# MDBT42Q.net
KiCad netlist of a schematic drawn in Altium Designer
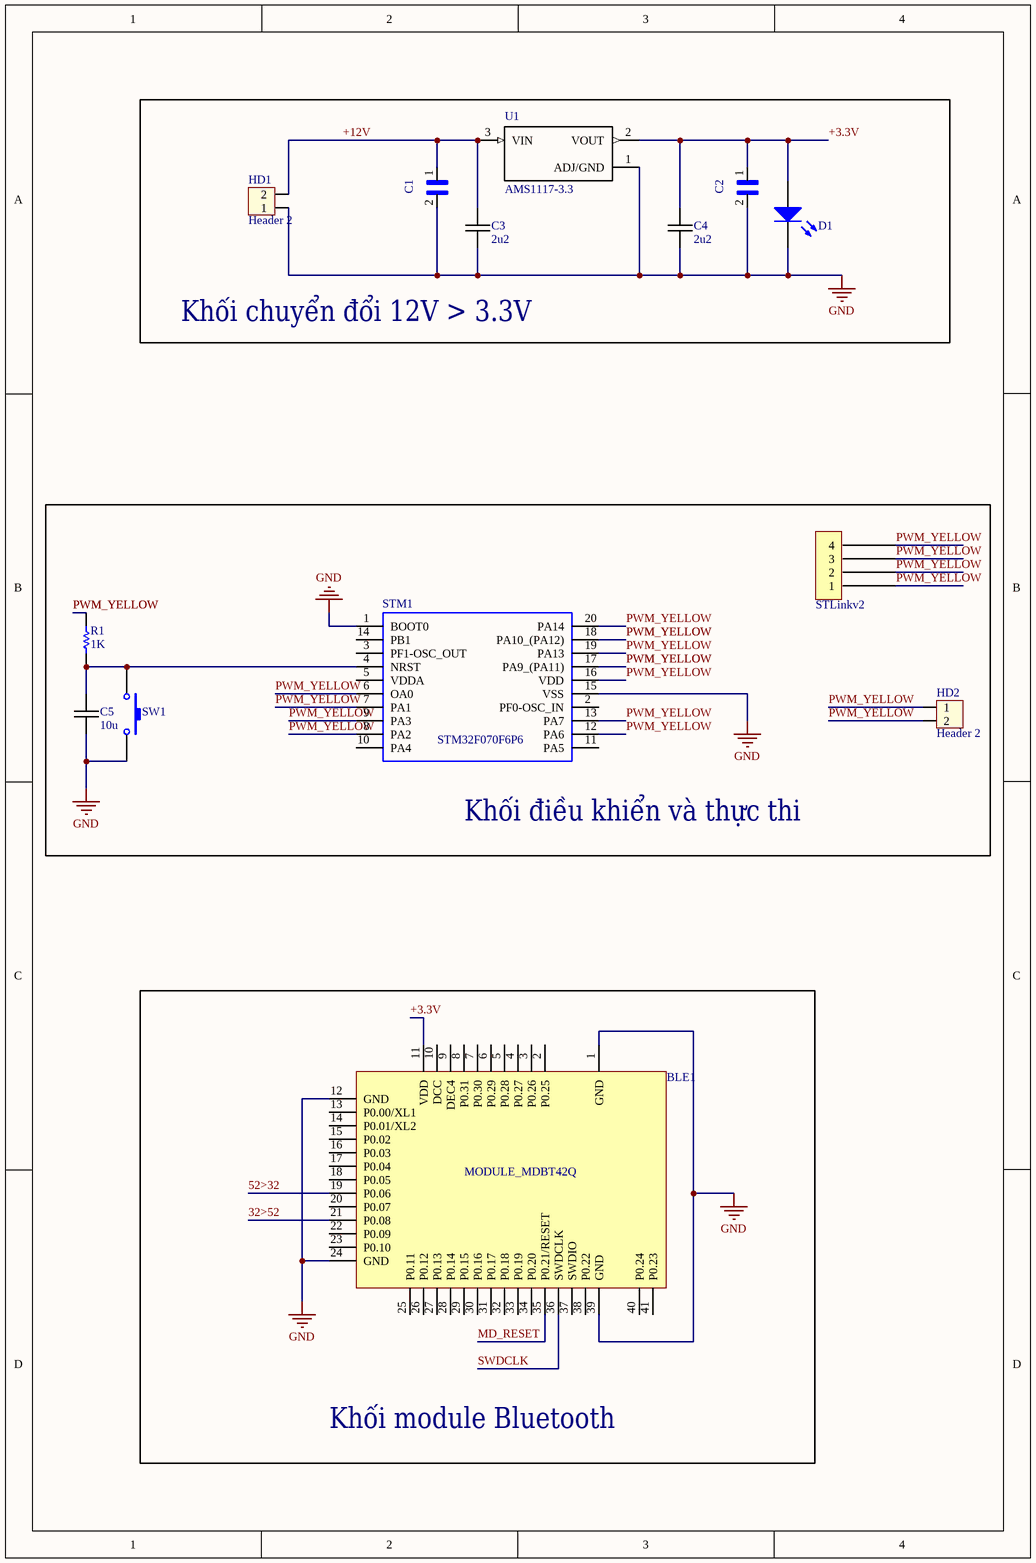
[diagram p0: MDBT42Q.SchDoc]

(export (version "E")
  (design (tool "Eeschema 10.0.6"))
  (components
    (comp (ref "BLE1")
      (value "MODULE_MDBT42Q")
      (footprint "PCB_MDBT42Q_10X16")
      (description "MDBT42Q")
      (libsource (lib "MDBT42Q_SCHLIB_160922") (part "MODULE_MDBT42Q"))
    )
    (comp (ref "C1")
      (value "C3216X5R1A106K160AB")
      (footprint "CAPC3216X180")
      (description "C Series 1206 10 uF 10 V Â±10 % Tolerance X5R SMT Multilayer Ceramic Capacitor")
      (fields (field (name "MF") "TDK"))
      (libsource (lib "C3216X5R1A106K160AB") (part "C3216X5R1A106K160AB"))
    )
    (comp (ref "C2")
      (value "C3216X5R1A106K160AB")
      (footprint "CAPC3216X180")
      (description "C Series 1206 10 uF 10 V Â±10 % Tolerance X5R SMT Multilayer Ceramic Capacitor")
      (fields (field (name "MF") "TDK"))
      (libsource (lib "C3216X5R1A106K160AB") (part "C3216X5R1A106K160AB"))
    )
    (comp (ref "C3")
      (value "2u2")
      (footprint "0805C-GENERIC")
      (description "CAPACITOR 0805 CERAMIC")
      (fields
        (field (name "MANUFACTURER PART NUMBER") "ECJ-1VB0J225K")
        (field (name "MANUFACTURER") "Panasonic - ECG")
      )
      (libsource (lib "vh_altium_library") (part "0805C-2U2-6V3-X5R-PAN"))
    )
    (comp (ref "C4")
      (value "2u2")
      (footprint "0805C-GENERIC")
      (description "CAPACITOR 0805 CERAMIC")
      (fields
        (field (name "MANUFACTURER PART NUMBER") "ECJ-1VB0J225K")
        (field (name "MANUFACTURER") "Panasonic - ECG")
      )
      (libsource (lib "vh_altium_library") (part "0805C-2U2-6V3-X5R-PAN"))
    )
    (comp (ref "C5")
      (value "10u")
      (footprint "0805C-GENERIC")
      (description "CAPACITOR 0805 CERAMIC")
      (fields
        (field (name "MANUFACTURER PART NUMBER") "ECJ-1VB0J225K")
        (field (name "MANUFACTURER") "Panasonic - ECG")
      )
      (libsource (lib "vh_altium_library") (part "0805C-2U2-6V3-X5R-PAN"))
    )
    (comp (ref "D1")
      (value "LED SMD")
      (footprint "LED_0805_Blue")
      (description "LED")
      (libsource (lib "PIF_Library") (part "LED SMD"))
    )
    (comp (ref "HD1")
      (value "Header 2")
      (footprint "HED2")
      (description "Header 2 (Green)")
      (libsource (lib "takahashi") (part "Hed2"))
    )
    (comp (ref "HD2")
      (value "Header 2")
      (footprint "HED2")
      (description "Header 2 (Green)")
      (libsource (lib "") (part "Hed2_1"))
    )
    (comp (ref "R1")
      (value "1K")
      (footprint "RES-SM-1206")
      (description "Resistor")
      (fields (field (name "Comment") "RESISTOR SMD"))
      (libsource (lib "PIF_Library") (part "RESISTOR SMD"))
    )
    (comp (ref "STLinkv2")
      (value "JP")
      (footprint "Jumper 4x1")
      (libsource (lib "jumper library Hoang loi") (part "Jumper 4x1"))
    )
    (comp (ref "STM1")
      (value "STM32F070F6P6")
      (footprint "SOP65P640X120-20N")
      (description "STMICROELECTRONICS - STM32F070F6P6 - MCU, 32BIT, CORTEX-M0, 48MHZ, TSSOP-20")
      (libsource (lib "STM32F070F6P6") (part "STM32F070F6P6"))
    )
    (comp (ref "SW1")
      (value "SW")
      (footprint "SW2")
      (description "Switch button 2 pin")
      (libsource (lib "PIF_Library") (part "Tact SW - 2Pin"))
    )
    (comp (ref "U1")
      (value "AMS1117-3.3")
      (footprint "SOT229P700X180-4N")
      (description "Sot223/Pkg 1-Amp 3.3-Volt Low Drop Out Voltage Regulatator")
      (fields (field (name "MF") "Advanced Monolithic Systems"))
      (libsource (lib "AMS1117-3.3") (part "AMS1117-3.3"))
    )
  )
  (nets
    (net (code "1") (name "/+3.3V") (class "Default")
      (node (ref "BLE1") (pin "11") (pinfunction "VDD_11") (pintype "passive"))
      (node (ref "C2") (pin "1") (pinfunction "1_1") (pintype "passive"))
      (node (ref "C4") (pin "1") (pintype "passive"))
      (node (ref "D1") (pin "1") (pinfunction "A_1") (pintype "passive"))
      (node (ref "U1") (pin "2") (pinfunction "VOUT_2") (pintype "output"))
    )
    (net (code "2") (name "/+12V") (class "Default")
      (node (ref "C1") (pin "1") (pinfunction "1_1") (pintype "passive"))
      (node (ref "C3") (pin "1") (pintype "passive"))
      (node (ref "HD1") (pin "2") (pinfunction "2_2") (pintype "passive"))
      (node (ref "U1") (pin "3") (pinfunction "VIN_3") (pintype "input"))
    )
    (net (code "3") (name "/32>52") (class "Default")
      (node (ref "BLE1") (pin "21") (pinfunction "P0.08_21") (pintype "passive"))
    )
    (net (code "4") (name "/52>32") (class "Default")
      (node (ref "BLE1") (pin "19") (pinfunction "P0.06_19") (pintype "passive"))
    )
    (net (code "5") (name "/MD_RESET") (class "Default")
      (node (ref "BLE1") (pin "35") (pinfunction "P0.21/RESET_35") (pintype "passive"))
    )
    (net (code "6") (name "/PWM_YELLOW") (class "Default")
      (node (ref "HD2") (pin "1") (pinfunction "1_1") (pintype "passive"))
      (node (ref "HD2") (pin "2") (pinfunction "2_2") (pintype "passive"))
      (node (ref "R1") (pin "2") (pinfunction "2_2") (pintype "passive"))
      (node (ref "STLinkv2") (pin "1") (pinfunction "1_1") (pintype "passive"))
      (node (ref "STLinkv2") (pin "2") (pinfunction "2_2") (pintype "passive"))
      (node (ref "STLinkv2") (pin "3") (pinfunction "3_3") (pintype "passive"))
      (node (ref "STLinkv2") (pin "4") (pinfunction "4_4") (pintype "passive"))
      (node (ref "STM1") (pin "12") (pinfunction "PA6_12") (pintype "passive"))
      (node (ref "STM1") (pin "13") (pinfunction "PA7_13") (pintype "passive"))
      (node (ref "STM1") (pin "16") (pinfunction "VDD_16") (pintype "passive"))
      (node (ref "STM1") (pin "17") (pinfunction "PA9_(PA11)_17") (pintype "passive"))
      (node (ref "STM1") (pin "18") (pinfunction "PA10_(PA12)_18") (pintype "passive"))
      (node (ref "STM1") (pin "19") (pinfunction "PA13_19") (pintype "passive"))
      (node (ref "STM1") (pin "20") (pinfunction "PA14_20") (pintype "passive"))
      (node (ref "STM1") (pin "6") (pinfunction "OA0_6") (pintype "passive"))
      (node (ref "STM1") (pin "7") (pinfunction "PA1_7") (pintype "passive"))
      (node (ref "STM1") (pin "8") (pinfunction "PA2_8") (pintype "passive"))
      (node (ref "STM1") (pin "9") (pinfunction "PA3_9") (pintype "passive"))
    )
    (net (code "7") (name "/SWDCLK") (class "Default")
      (node (ref "BLE1") (pin "36") (pinfunction "SWDCLK_36") (pintype "passive"))
    )
    (net (code "8") (name "GND") (class "Default")
      (node (ref "BLE1") (pin "1") (pinfunction "GND_1") (pintype "passive"))
      (node (ref "BLE1") (pin "12") (pinfunction "GND_12") (pintype "passive"))
      (node (ref "BLE1") (pin "24") (pinfunction "GND_24") (pintype "passive"))
      (node (ref "BLE1") (pin "39") (pinfunction "GND_39") (pintype "passive"))
      (node (ref "C1") (pin "2") (pinfunction "2_2") (pintype "passive"))
      (node (ref "C2") (pin "2") (pinfunction "2_2") (pintype "passive"))
      (node (ref "C3") (pin "2") (pintype "passive"))
      (node (ref "C4") (pin "2") (pintype "passive"))
      (node (ref "C5") (pin "2") (pintype "passive"))
      (node (ref "D1") (pin "2") (pinfunction "K_2") (pintype "passive"))
      (node (ref "HD1") (pin "1") (pinfunction "1_1") (pintype "passive"))
      (node (ref "STM1") (pin "1") (pinfunction "BOOT0_1") (pintype "passive"))
      (node (ref "STM1") (pin "15") (pinfunction "VSS_15") (pintype "passive"))
      (node (ref "SW1") (pin "2") (pinfunction "2_2") (pintype "passive"))
      (node (ref "U1") (pin "1") (pinfunction "ADJ/GND_1") (pintype "power_in"))
    )
    (net (code "9") (name "Net-(STM1-NRST)") (class "Default")
      (node (ref "C5") (pin "1") (pintype "passive"))
      (node (ref "R1") (pin "1") (pinfunction "1_1") (pintype "passive"))
      (node (ref "STM1") (pin "4") (pinfunction "NRST_4") (pintype "passive"))
      (node (ref "SW1") (pin "1") (pinfunction "1_1") (pintype "passive"))
    )
    (net (code "10") (name "unconnected-(BLE1-DCC-Pad10)") (class "Default")
      (node (ref "BLE1") (pin "10") (pinfunction "DCC_10") (pintype "passive"))
    )
    (net (code "11") (name "unconnected-(BLE1-DEC4-Pad9)") (class "Default")
      (node (ref "BLE1") (pin "9") (pinfunction "DEC4_9") (pintype "passive"))
    )
    (net (code "12") (name "unconnected-(BLE1-P0.00{slash}XL1-Pad13)") (class "Default")
      (node (ref "BLE1") (pin "13") (pinfunction "P0.00/XL1_13") (pintype "passive"))
    )
    (net (code "13") (name "unconnected-(BLE1-P0.01{slash}XL2-Pad14)") (class "Default")
      (node (ref "BLE1") (pin "14") (pinfunction "P0.01/XL2_14") (pintype "passive"))
    )
    (net (code "14") (name "unconnected-(BLE1-P0.02-Pad15)") (class "Default")
      (node (ref "BLE1") (pin "15") (pinfunction "P0.02_15") (pintype "passive"))
    )
    (net (code "15") (name "unconnected-(BLE1-P0.03-Pad16)") (class "Default")
      (node (ref "BLE1") (pin "16") (pinfunction "P0.03_16") (pintype "passive"))
    )
    (net (code "16") (name "unconnected-(BLE1-P0.04-Pad17)") (class "Default")
      (node (ref "BLE1") (pin "17") (pinfunction "P0.04_17") (pintype "passive"))
    )
    (net (code "17") (name "unconnected-(BLE1-P0.05-Pad18)") (class "Default")
      (node (ref "BLE1") (pin "18") (pinfunction "P0.05_18") (pintype "passive"))
    )
    (net (code "18") (name "unconnected-(BLE1-P0.07-Pad20)") (class "Default")
      (node (ref "BLE1") (pin "20") (pinfunction "P0.07_20") (pintype "passive"))
    )
    (net (code "19") (name "unconnected-(BLE1-P0.09-Pad22)") (class "Default")
      (node (ref "BLE1") (pin "22") (pinfunction "P0.09_22") (pintype "passive"))
    )
    (net (code "20") (name "unconnected-(BLE1-P0.10-Pad23)") (class "Default")
      (node (ref "BLE1") (pin "23") (pinfunction "P0.10_23") (pintype "passive"))
    )
    (net (code "21") (name "unconnected-(BLE1-P0.11-Pad25)") (class "Default")
      (node (ref "BLE1") (pin "25") (pinfunction "P0.11_25") (pintype "passive"))
    )
    (net (code "22") (name "unconnected-(BLE1-P0.12-Pad26)") (class "Default")
      (node (ref "BLE1") (pin "26") (pinfunction "P0.12_26") (pintype "passive"))
    )
    (net (code "23") (name "unconnected-(BLE1-P0.13-Pad27)") (class "Default")
      (node (ref "BLE1") (pin "27") (pinfunction "P0.13_27") (pintype "passive"))
    )
    (net (code "24") (name "unconnected-(BLE1-P0.14-Pad28)") (class "Default")
      (node (ref "BLE1") (pin "28") (pinfunction "P0.14_28") (pintype "passive"))
    )
    (net (code "25") (name "unconnected-(BLE1-P0.15-Pad29)") (class "Default")
      (node (ref "BLE1") (pin "29") (pinfunction "P0.15_29") (pintype "passive"))
    )
    (net (code "26") (name "unconnected-(BLE1-P0.16-Pad30)") (class "Default")
      (node (ref "BLE1") (pin "30") (pinfunction "P0.16_30") (pintype "passive"))
    )
    (net (code "27") (name "unconnected-(BLE1-P0.17-Pad31)") (class "Default")
      (node (ref "BLE1") (pin "31") (pinfunction "P0.17_31") (pintype "passive"))
    )
    (net (code "28") (name "unconnected-(BLE1-P0.18-Pad32)") (class "Default")
      (node (ref "BLE1") (pin "32") (pinfunction "P0.18_32") (pintype "passive"))
    )
    (net (code "29") (name "unconnected-(BLE1-P0.19-Pad33)") (class "Default")
      (node (ref "BLE1") (pin "33") (pinfunction "P0.19_33") (pintype "passive"))
    )
    (net (code "30") (name "unconnected-(BLE1-P0.20-Pad34)") (class "Default")
      (node (ref "BLE1") (pin "34") (pinfunction "P0.20_34") (pintype "passive"))
    )
    (net (code "31") (name "unconnected-(BLE1-P0.22-Pad38)") (class "Default")
      (node (ref "BLE1") (pin "38") (pinfunction "P0.22_38") (pintype "passive"))
    )
    (net (code "32") (name "unconnected-(BLE1-P0.23-Pad41)") (class "Default")
      (node (ref "BLE1") (pin "41") (pinfunction "P0.23_41") (pintype "passive"))
    )
    (net (code "33") (name "unconnected-(BLE1-P0.24-Pad40)") (class "Default")
      (node (ref "BLE1") (pin "40") (pinfunction "P0.24_40") (pintype "passive"))
    )
    (net (code "34") (name "unconnected-(BLE1-P0.25-Pad2)") (class "Default")
      (node (ref "BLE1") (pin "2") (pinfunction "P0.25_2") (pintype "passive"))
    )
    (net (code "35") (name "unconnected-(BLE1-P0.26-Pad3)") (class "Default")
      (node (ref "BLE1") (pin "3") (pinfunction "P0.26_3") (pintype "passive"))
    )
    (net (code "36") (name "unconnected-(BLE1-P0.27-Pad4)") (class "Default")
      (node (ref "BLE1") (pin "4") (pinfunction "P0.27_4") (pintype "passive"))
    )
    (net (code "37") (name "unconnected-(BLE1-P0.28-Pad5)") (class "Default")
      (node (ref "BLE1") (pin "5") (pinfunction "P0.28_5") (pintype "passive"))
    )
    (net (code "38") (name "unconnected-(BLE1-P0.29-Pad6)") (class "Default")
      (node (ref "BLE1") (pin "6") (pinfunction "P0.29_6") (pintype "passive"))
    )
    (net (code "39") (name "unconnected-(BLE1-P0.30-Pad7)") (class "Default")
      (node (ref "BLE1") (pin "7") (pinfunction "P0.30_7") (pintype "passive"))
    )
    (net (code "40") (name "unconnected-(BLE1-P0.31-Pad8)") (class "Default")
      (node (ref "BLE1") (pin "8") (pinfunction "P0.31_8") (pintype "passive"))
    )
    (net (code "41") (name "unconnected-(BLE1-SWDIO-Pad37)") (class "Default")
      (node (ref "BLE1") (pin "37") (pinfunction "SWDIO_37") (pintype "passive"))
    )
    (net (code "42") (name "unconnected-(STM1-PA4-Pad10)") (class "Default")
      (node (ref "STM1") (pin "10") (pinfunction "PA4_10") (pintype "passive"))
    )
    (net (code "43") (name "unconnected-(STM1-PA5-Pad11)") (class "Default")
      (node (ref "STM1") (pin "11") (pinfunction "PA5_11") (pintype "passive"))
    )
    (net (code "44") (name "unconnected-(STM1-PB1-Pad14)") (class "Default")
      (node (ref "STM1") (pin "14") (pinfunction "PB1_14") (pintype "passive"))
    )
    (net (code "45") (name "unconnected-(STM1-PF0-OSC_IN-Pad2)") (class "Default")
      (node (ref "STM1") (pin "2") (pinfunction "PF0-OSC_IN_2") (pintype "passive"))
    )
    (net (code "46") (name "unconnected-(STM1-PF1-OSC_OUT-Pad3)") (class "Default")
      (node (ref "STM1") (pin "3") (pinfunction "PF1-OSC_OUT_3") (pintype "passive"))
    )
    (net (code "47") (name "unconnected-(STM1-VDDA-Pad5)") (class "Default")
      (node (ref "STM1") (pin "5") (pinfunction "VDDA_5") (pintype "passive"))
    )
  )
)
